# 3_3V_Regulator.net
KiCad netlist of a schematic drawn in Altium Designer
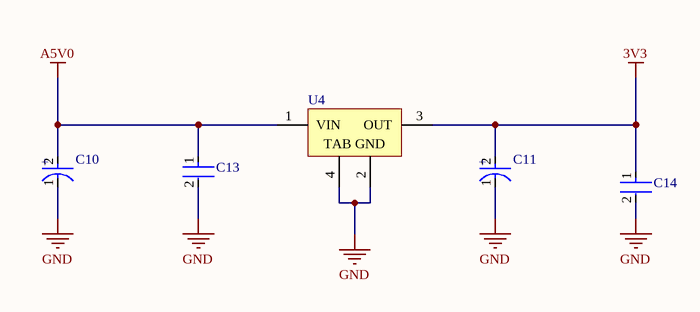
[diagram p0: 3.3V_Regulator.SchDoc]

(export (version "E")
  (design (tool "Eeschema 10.0.6"))
  (components
    (comp (ref "C10")
      (value "UUR1C221MCL6GS")
      (footprint "FP-UUR1C221MCL6GS-MFG")
      (description "Cap Aluminum Lytic 220uF 16V 20% (6.3 X 7.7mm) SMD 162mA 2000h 85C T/R")
      (fields (field (name "MANUFACTURER") "Nichicon") (field (name "TOLERANCE") "20%"))
      (libsource (lib "Replacements") (part "UUR1C221MCL6GS"))
    )
    (comp (ref "C11")
      (value "UUR1C221MCL6GS")
      (footprint "FP-UUR1C221MCL6GS-MFG")
      (description "Cap Aluminum Lytic 220uF 16V 20% (6.3 X 7.7mm) SMD 162mA 2000h 85C T/R")
      (fields (field (name "MANUFACTURER") "Nichicon") (field (name "TOLERANCE") "20%"))
      (libsource (lib "Replacements") (part "UUR1C221MCL6GS"))
    )
    (comp (ref "C13")
      (value "GRM022R60J104ME15L")
      (footprint "CAPC0402X22N")
      (description "Multilayer Ceramic Capacitors (MLCC) - SMD/SMT 50volts 0.1uF X7R 10%")
      (fields
        (field (name "MANUFACTURER") "KEMET")
        (field (name "MANUFACTURER PART NUMBER") "C0603C104K5RACTU")
      )
      (libsource (lib "Replacements") (part "C0603C104K5RACTU"))
    )
    (comp (ref "C14")
      (value "GRM022R60J104ME15L")
      (footprint "CAPC2012X88N")
      (description "Multilayer Ceramic Capacitors (MLCC) - SMD/SMT 50volts 0.1uF X7R 10%")
      (fields
        (field (name "MANUFACTURER") "KEMET")
        (field (name "MANUFACTURER PART NUMBER") "C0603C104K5RACTU")
      )
      (libsource (lib "Replacements") (part "C0603C104K5RACTU"))
    )
    (comp (ref "U4")
      (value "LT1121CST-3.3#TRPBF")
      (footprint "LT-ST-3-SOT-223_N")
      (fields (field (name "MANUFACTURER") "Linear Technology"))
      (libsource (lib "Altium Content Vault") (part "LT-LT112X-ST-3"))
    )
  )
  (nets
    (net (code "1") (name "3V3") (class "Default")
      (node (ref "C11") (pin "2") (pinfunction "A_2") (pintype "passive"))
      (node (ref "C14") (pin "1") (pinfunction "1_1") (pintype "passive"))
      (node (ref "U4") (pin "3") (pinfunction "OUT_3") (pintype "power_in"))
    )
    (net (code "2") (name "A5V0") (class "Default")
      (node (ref "C10") (pin "2") (pinfunction "A_2") (pintype "passive"))
      (node (ref "C13") (pin "1") (pinfunction "1_1") (pintype "passive"))
      (node (ref "U4") (pin "1") (pinfunction "VIN_1") (pintype "power_in"))
    )
    (net (code "3") (name "GND") (class "Default")
      (node (ref "C10") (pin "1") (pinfunction "C_1") (pintype "passive"))
      (node (ref "C11") (pin "1") (pinfunction "C_1") (pintype "passive"))
      (node (ref "C13") (pin "2") (pinfunction "2_2") (pintype "passive"))
      (node (ref "C14") (pin "2") (pinfunction "2_2") (pintype "passive"))
      (node (ref "U4") (pin "2") (pinfunction "GND_2") (pintype "power_in"))
      (node (ref "U4") (pin "4") (pinfunction "TAB_4") (pintype "power_in"))
    )
  )
)
